# Version_04.net
KiCad netlist of a schematic drawn in EAGLE
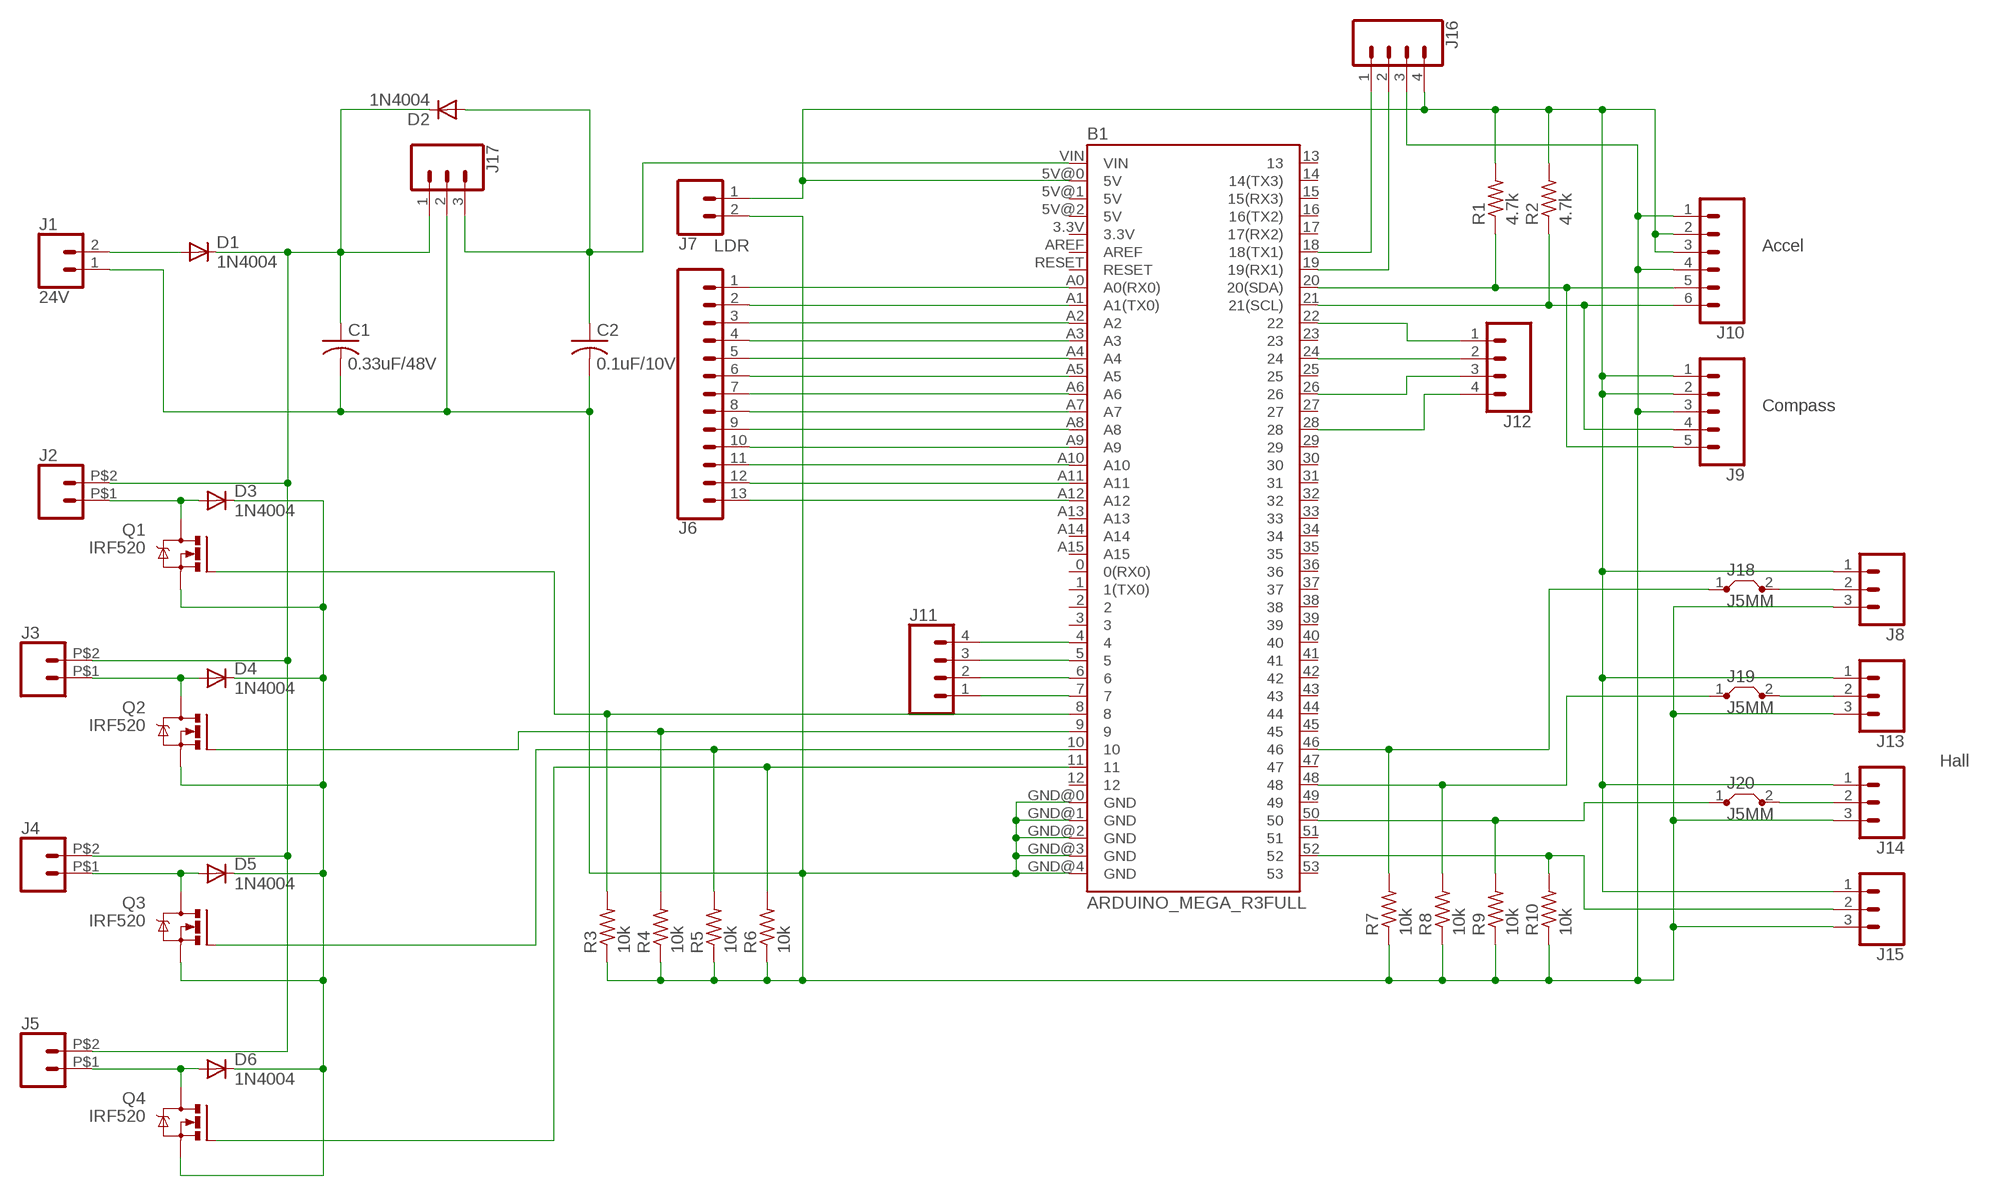
[diagram p0: schematic, sheet 1]

(export (version "E")
  (design (tool "Eeschema 10.0.6"))
  (components
    (comp (ref "B1")
      (value "ARDUINO_MEGA_R3FULL")
      (footprint "eagle-import:ARDUINO_MEGA")
      (libsource (lib "eagle-import") (part "ARDUINO_MEGA_R3FULL"))
    )
    (comp (ref "C1")
      (value "0.33uF/48V")
      (footprint "eagle-import:C050-075X075")
      (libsource (lib "eagle-import") (part "C-US050-075X075"))
    )
    (comp (ref "C2")
      (value "0.1uF/10V")
      (footprint "eagle-import:C025-060X050")
      (libsource (lib "eagle-import") (part "C-US025-060X050"))
    )
    (comp (ref "D1")
      (value "1N4004")
      (footprint "eagle-import:DO41-10")
      (libsource (lib "eagle-import") (part "1N4004"))
    )
    (comp (ref "D2")
      (value "1N4004")
      (footprint "eagle-import:DO41-10")
      (libsource (lib "eagle-import") (part "1N4004"))
    )
    (comp (ref "D3")
      (value "1N4004")
      (footprint "eagle-import:DO41-10")
      (libsource (lib "eagle-import") (part "1N4004"))
    )
    (comp (ref "D4")
      (value "1N4004")
      (footprint "eagle-import:DO41-10")
      (libsource (lib "eagle-import") (part "1N4004"))
    )
    (comp (ref "D5")
      (value "1N4004")
      (footprint "eagle-import:DO41-10")
      (libsource (lib "eagle-import") (part "1N4004"))
    )
    (comp (ref "D6")
      (value "1N4004")
      (footprint "eagle-import:DO41-10")
      (libsource (lib "eagle-import") (part "1N4004"))
    )
    (comp (ref "J1")
      (value "24V")
      (footprint "eagle-import:SCREWTERMINAL-3.5MM-2_LOCK")
      (libsource (lib "eagle-import") (part "CONN_023.5MM_LOCK"))
    )
    (comp (ref "J2")
      (value "CONN_02PTH2")
      (footprint "eagle-import:1X02_BIG")
      (libsource (lib "eagle-import") (part "CONN_02PTH2"))
    )
    (comp (ref "J3")
      (value "CONN_02PTH2")
      (footprint "eagle-import:1X02_BIG")
      (libsource (lib "eagle-import") (part "CONN_02PTH2"))
    )
    (comp (ref "J4")
      (value "CONN_02PTH2")
      (footprint "eagle-import:1X02_BIG")
      (libsource (lib "eagle-import") (part "CONN_02PTH2"))
    )
    (comp (ref "J5")
      (value "CONN_02PTH2")
      (footprint "eagle-import:1X02_BIG")
      (libsource (lib "eagle-import") (part "CONN_02PTH2"))
    )
    (comp (ref "J6")
      (value "CONN_13LONGPADS")
      (footprint "eagle-import:1X13-LONGPADS")
      (libsource (lib "eagle-import") (part "CONN_13LONGPADS"))
    )
    (comp (ref "J7")
      (value "CONN_02LOCK_LONGPADS")
      (footprint "eagle-import:1X02_LOCK_LONGPADS")
      (libsource (lib "eagle-import") (part "CONN_02LOCK_LONGPADS"))
    )
    (comp (ref "J8")
      (value "CONN_03LONGPADS")
      (footprint "eagle-import:1X03_LONGPADS")
      (libsource (lib "eagle-import") (part "CONN_03LONGPADS"))
    )
    (comp (ref "J9")
      (value "CONN_05PTH_LONGPADS")
      (footprint "eagle-import:1X05_LONGPADS")
      (libsource (lib "eagle-import") (part "CONN_05PTH_LONGPADS"))
    )
    (comp (ref "J10")
      (value "CONN_06LONGPADS")
      (footprint "eagle-import:1X06_LONGPADS")
      (libsource (lib "eagle-import") (part "CONN_06LONGPADS"))
    )
    (comp (ref "J11")
      (value "CONN_04LONGPADS")
      (footprint "eagle-import:1X04_LONGPADS")
      (libsource (lib "eagle-import") (part "CONN_04LONGPADS"))
    )
    (comp (ref "J12")
      (value "CONN_04LONGPADS")
      (footprint "eagle-import:1X04_LONGPADS")
      (libsource (lib "eagle-import") (part "CONN_04LONGPADS"))
    )
    (comp (ref "J13")
      (value "CONN_03LONGPADS")
      (footprint "eagle-import:1X03_LONGPADS")
      (libsource (lib "eagle-import") (part "CONN_03LONGPADS"))
    )
    (comp (ref "J14")
      (value "CONN_03LONGPADS")
      (footprint "eagle-import:1X03_LONGPADS")
      (libsource (lib "eagle-import") (part "CONN_03LONGPADS"))
    )
    (comp (ref "J15")
      (value "CONN_03LONGPADS")
      (footprint "eagle-import:1X03_LONGPADS")
      (libsource (lib "eagle-import") (part "CONN_03LONGPADS"))
    )
    (comp (ref "J16")
      (value "CONN_04LONGPADS")
      (footprint "eagle-import:1X04_LONGPADS")
      (libsource (lib "eagle-import") (part "CONN_04LONGPADS"))
    )
    (comp (ref "J17")
      (value "CONN_03LONGPADS")
      (footprint "eagle-import:1X03_LONGPADS")
      (libsource (lib "eagle-import") (part "CONN_03LONGPADS"))
    )
    (comp (ref "J18")
      (value "J5MM")
      (footprint "eagle-import:05")
      (libsource (lib "eagle-import") (part "J5MM"))
    )
    (comp (ref "J19")
      (value "J5MM")
      (footprint "eagle-import:05")
      (libsource (lib "eagle-import") (part "J5MM"))
    )
    (comp (ref "J20")
      (value "J5MM")
      (footprint "eagle-import:05")
      (libsource (lib "eagle-import") (part "J5MM"))
    )
    (comp (ref "Q1")
      (value "IRF520")
      (footprint "eagle-import:TO220BV")
      (libsource (lib "eagle-import") (part "IRF520"))
    )
    (comp (ref "Q2")
      (value "IRF520")
      (footprint "eagle-import:TO220BV")
      (libsource (lib "eagle-import") (part "IRF520"))
    )
    (comp (ref "Q3")
      (value "IRF520")
      (footprint "eagle-import:TO220BV")
      (libsource (lib "eagle-import") (part "IRF520"))
    )
    (comp (ref "Q4")
      (value "IRF520")
      (footprint "eagle-import:TO220BV")
      (libsource (lib "eagle-import") (part "IRF520"))
    )
    (comp (ref "R1")
      (value "4.7k")
      (footprint "eagle-import:0207_7")
      (libsource (lib "eagle-import") (part "resistor_R-US_0207/7"))
    )
    (comp (ref "R2")
      (value "4.7k")
      (footprint "eagle-import:0207_7")
      (libsource (lib "eagle-import") (part "resistor_R-US_0207/7"))
    )
    (comp (ref "R3")
      (value "10k")
      (footprint "eagle-import:0207_10")
      (libsource (lib "eagle-import") (part "rcl_R-US_0207/10"))
    )
    (comp (ref "R4")
      (value "10k")
      (footprint "eagle-import:0207_10")
      (libsource (lib "eagle-import") (part "rcl_R-US_0207/10"))
    )
    (comp (ref "R5")
      (value "10k")
      (footprint "eagle-import:0207_10")
      (libsource (lib "eagle-import") (part "rcl_R-US_0207/10"))
    )
    (comp (ref "R6")
      (value "10k")
      (footprint "eagle-import:0207_10")
      (libsource (lib "eagle-import") (part "rcl_R-US_0207/10"))
    )
    (comp (ref "R7")
      (value "10k")
      (footprint "eagle-import:0207_10")
      (libsource (lib "eagle-import") (part "R-US_0207/10"))
    )
    (comp (ref "R8")
      (value "10k")
      (footprint "eagle-import:0207_10")
      (libsource (lib "eagle-import") (part "R-US_0207/10"))
    )
    (comp (ref "R9")
      (value "10k")
      (footprint "eagle-import:0207_10")
      (libsource (lib "eagle-import") (part "R-US_0207/10"))
    )
    (comp (ref "R10")
      (value "10k")
      (footprint "eagle-import:0207_10")
      (libsource (lib "eagle-import") (part "R-US_0207/10"))
    )
  )
  (nets
    (net (code "1") (name "Net-(B1-5V-Pad5V@0)") (class "Default")
      (node (ref "B1") (pin "5V@0") (pinfunction "5V_5V@0") (pintype "bidirectional"))
      (node (ref "J10") (pin "2") (pinfunction "2_2") (pintype "passive"))
      (node (ref "J10") (pin "3") (pinfunction "3_3") (pintype "passive"))
      (node (ref "J13") (pin "1") (pinfunction "1_1") (pintype "passive"))
      (node (ref "J14") (pin "1") (pinfunction "1_1") (pintype "passive"))
      (node (ref "J15") (pin "1") (pinfunction "1_1") (pintype "passive"))
      (node (ref "J16") (pin "4") (pinfunction "4_4") (pintype "passive"))
      (node (ref "J7") (pin "1") (pinfunction "1_1") (pintype "passive"))
      (node (ref "J8") (pin "1") (pinfunction "1_1") (pintype "passive"))
      (node (ref "J9") (pin "1") (pinfunction "1_1") (pintype "passive"))
      (node (ref "J9") (pin "2") (pinfunction "2_2") (pintype "passive"))
      (node (ref "R1") (pin "2") (pinfunction "2_2") (pintype "passive"))
      (node (ref "R2") (pin "2") (pinfunction "2_2") (pintype "passive"))
    )
    (net (code "2") (name "Net-(B1-18(TX1))") (class "Default")
      (node (ref "B1") (pin "18") (pinfunction "18(TX1)_18") (pintype "bidirectional"))
      (node (ref "J16") (pin "1") (pinfunction "1_1") (pintype "passive"))
    )
    (net (code "3") (name "Net-(B1-19(RX1))") (class "Default")
      (node (ref "B1") (pin "19") (pinfunction "19(RX1)_19") (pintype "bidirectional"))
      (node (ref "J16") (pin "2") (pinfunction "2_2") (pintype "passive"))
    )
    (net (code "4") (name "Net-(B1-20(SDA))") (class "Default")
      (node (ref "B1") (pin "20") (pinfunction "20(SDA)_20") (pintype "bidirectional"))
      (node (ref "J10") (pin "5") (pinfunction "5_5") (pintype "passive"))
      (node (ref "J9") (pin "5") (pinfunction "5_5") (pintype "passive"))
      (node (ref "R1") (pin "1") (pinfunction "1_1") (pintype "passive"))
    )
    (net (code "5") (name "Net-(B1-21(SCL))") (class "Default")
      (node (ref "B1") (pin "21") (pinfunction "21(SCL)_21") (pintype "bidirectional"))
      (node (ref "J10") (pin "6") (pinfunction "6_6") (pintype "passive"))
      (node (ref "J9") (pin "4") (pinfunction "4_4") (pintype "passive"))
      (node (ref "R2") (pin "1") (pinfunction "1_1") (pintype "passive"))
    )
    (net (code "6") (name "Net-(B1-A0(RX0))") (class "Default")
      (node (ref "B1") (pin "A0") (pinfunction "A0(RX0)_A0") (pintype "bidirectional"))
      (node (ref "J6") (pin "1") (pinfunction "1_1") (pintype "passive"))
    )
    (net (code "7") (name "Net-(B1-A1(TX0))") (class "Default")
      (node (ref "B1") (pin "A1") (pinfunction "A1(TX0)_A1") (pintype "bidirectional"))
      (node (ref "J6") (pin "2") (pinfunction "2_2") (pintype "passive"))
    )
    (net (code "8") (name "Net-(B1-GND-PadGND@0)") (class "Default")
      (node (ref "B1") (pin "GND@0") (pinfunction "GND_GND@0") (pintype "bidirectional"))
      (node (ref "B1") (pin "GND@1") (pinfunction "GND_GND@1") (pintype "bidirectional"))
      (node (ref "B1") (pin "GND@2") (pinfunction "GND_GND@2") (pintype "bidirectional"))
      (node (ref "B1") (pin "GND@3") (pinfunction "GND_GND@3") (pintype "bidirectional"))
      (node (ref "B1") (pin "GND@4") (pinfunction "GND_GND@4") (pintype "bidirectional"))
      (node (ref "C1") (pin "2") (pinfunction "2_2") (pintype "passive"))
      (node (ref "C2") (pin "2") (pinfunction "2_2") (pintype "passive"))
      (node (ref "J1") (pin "1") (pinfunction "1_1") (pintype "passive"))
      (node (ref "J10") (pin "1") (pinfunction "1_1") (pintype "passive"))
      (node (ref "J10") (pin "4") (pinfunction "4_4") (pintype "passive"))
      (node (ref "J13") (pin "3") (pinfunction "3_3") (pintype "passive"))
      (node (ref "J14") (pin "3") (pinfunction "3_3") (pintype "passive"))
      (node (ref "J15") (pin "3") (pinfunction "3_3") (pintype "passive"))
      (node (ref "J16") (pin "3") (pinfunction "3_3") (pintype "passive"))
      (node (ref "J17") (pin "2") (pinfunction "2_2") (pintype "passive"))
      (node (ref "J7") (pin "2") (pinfunction "2_2") (pintype "passive"))
      (node (ref "J8") (pin "3") (pinfunction "3_3") (pintype "passive"))
      (node (ref "J9") (pin "3") (pinfunction "3_3") (pintype "passive"))
      (node (ref "R10") (pin "1") (pinfunction "1_1") (pintype "passive"))
      (node (ref "R3") (pin "1") (pinfunction "1_1") (pintype "passive"))
      (node (ref "R4") (pin "1") (pinfunction "1_1") (pintype "passive"))
      (node (ref "R5") (pin "1") (pinfunction "1_1") (pintype "passive"))
      (node (ref "R6") (pin "1") (pinfunction "1_1") (pintype "passive"))
      (node (ref "R7") (pin "1") (pinfunction "1_1") (pintype "passive"))
      (node (ref "R8") (pin "1") (pinfunction "1_1") (pintype "passive"))
      (node (ref "R9") (pin "1") (pinfunction "1_1") (pintype "passive"))
    )
    (net (code "9") (name "Net-(B1-Pad4)") (class "Default")
      (node (ref "B1") (pin "4") (pinfunction "4_4") (pintype "bidirectional"))
      (node (ref "J11") (pin "4") (pinfunction "4_4") (pintype "passive"))
    )
    (net (code "10") (name "Net-(B1-Pad5)") (class "Default")
      (node (ref "B1") (pin "5") (pinfunction "5_5") (pintype "bidirectional"))
      (node (ref "J11") (pin "3") (pinfunction "3_3") (pintype "passive"))
    )
    (net (code "11") (name "Net-(B1-Pad6)") (class "Default")
      (node (ref "B1") (pin "6") (pinfunction "6_6") (pintype "bidirectional"))
      (node (ref "J11") (pin "2") (pinfunction "2_2") (pintype "passive"))
    )
    (net (code "12") (name "Net-(B1-Pad7)") (class "Default")
      (node (ref "B1") (pin "7") (pinfunction "7_7") (pintype "bidirectional"))
      (node (ref "J11") (pin "1") (pinfunction "1_1") (pintype "passive"))
    )
    (net (code "13") (name "Net-(B1-Pad8)") (class "Default")
      (node (ref "B1") (pin "8") (pinfunction "8_8") (pintype "bidirectional"))
      (node (ref "Q1") (pin "G") (pinfunction "G_G") (pintype "passive"))
      (node (ref "R3") (pin "2") (pinfunction "2_2") (pintype "passive"))
    )
    (net (code "14") (name "Net-(B1-Pad9)") (class "Default")
      (node (ref "B1") (pin "9") (pinfunction "9_9") (pintype "bidirectional"))
      (node (ref "Q2") (pin "G") (pinfunction "G_G") (pintype "passive"))
      (node (ref "R4") (pin "2") (pinfunction "2_2") (pintype "passive"))
    )
    (net (code "15") (name "Net-(B1-Pad10)") (class "Default")
      (node (ref "B1") (pin "10") (pinfunction "10_10") (pintype "bidirectional"))
      (node (ref "Q3") (pin "G") (pinfunction "G_G") (pintype "passive"))
      (node (ref "R5") (pin "2") (pinfunction "2_2") (pintype "passive"))
    )
    (net (code "16") (name "Net-(B1-Pad11)") (class "Default")
      (node (ref "B1") (pin "11") (pinfunction "11_11") (pintype "bidirectional"))
      (node (ref "Q4") (pin "G") (pinfunction "G_G") (pintype "passive"))
      (node (ref "R6") (pin "2") (pinfunction "2_2") (pintype "passive"))
    )
    (net (code "17") (name "Net-(B1-Pad22)") (class "Default")
      (node (ref "B1") (pin "22") (pinfunction "22_22") (pintype "bidirectional"))
      (node (ref "J12") (pin "1") (pinfunction "1_1") (pintype "passive"))
    )
    (net (code "18") (name "Net-(B1-Pad24)") (class "Default")
      (node (ref "B1") (pin "24") (pinfunction "24_24") (pintype "bidirectional"))
      (node (ref "J12") (pin "2") (pinfunction "2_2") (pintype "passive"))
    )
    (net (code "19") (name "Net-(B1-Pad26)") (class "Default")
      (node (ref "B1") (pin "26") (pinfunction "26_26") (pintype "bidirectional"))
      (node (ref "J12") (pin "3") (pinfunction "3_3") (pintype "passive"))
    )
    (net (code "20") (name "Net-(B1-Pad28)") (class "Default")
      (node (ref "B1") (pin "28") (pinfunction "28_28") (pintype "bidirectional"))
      (node (ref "J12") (pin "4") (pinfunction "4_4") (pintype "passive"))
    )
    (net (code "21") (name "Net-(B1-Pad46)") (class "Default")
      (node (ref "B1") (pin "46") (pinfunction "46_46") (pintype "bidirectional"))
      (node (ref "J18") (pin "1") (pinfunction "1_1") (pintype "passive"))
      (node (ref "R7") (pin "2") (pinfunction "2_2") (pintype "passive"))
    )
    (net (code "22") (name "Net-(B1-Pad48)") (class "Default")
      (node (ref "B1") (pin "48") (pinfunction "48_48") (pintype "bidirectional"))
      (node (ref "J19") (pin "1") (pinfunction "1_1") (pintype "passive"))
      (node (ref "R8") (pin "2") (pinfunction "2_2") (pintype "passive"))
    )
    (net (code "23") (name "Net-(B1-Pad50)") (class "Default")
      (node (ref "B1") (pin "50") (pinfunction "50_50") (pintype "bidirectional"))
      (node (ref "J20") (pin "1") (pinfunction "1_1") (pintype "passive"))
      (node (ref "R9") (pin "2") (pinfunction "2_2") (pintype "passive"))
    )
    (net (code "24") (name "Net-(B1-Pad52)") (class "Default")
      (node (ref "B1") (pin "52") (pinfunction "52_52") (pintype "bidirectional"))
      (node (ref "J15") (pin "2") (pinfunction "2_2") (pintype "passive"))
      (node (ref "R10") (pin "2") (pinfunction "2_2") (pintype "passive"))
    )
    (net (code "25") (name "Net-(B1-PadA2)") (class "Default")
      (node (ref "B1") (pin "A2") (pinfunction "A2_A2") (pintype "bidirectional"))
      (node (ref "J6") (pin "3") (pinfunction "3_3") (pintype "passive"))
    )
    (net (code "26") (name "Net-(B1-PadA3)") (class "Default")
      (node (ref "B1") (pin "A3") (pinfunction "A3_A3") (pintype "bidirectional"))
      (node (ref "J6") (pin "4") (pinfunction "4_4") (pintype "passive"))
    )
    (net (code "27") (name "Net-(B1-PadA4)") (class "Default")
      (node (ref "B1") (pin "A4") (pinfunction "A4_A4") (pintype "bidirectional"))
      (node (ref "J6") (pin "5") (pinfunction "5_5") (pintype "passive"))
    )
    (net (code "28") (name "Net-(B1-PadA5)") (class "Default")
      (node (ref "B1") (pin "A5") (pinfunction "A5_A5") (pintype "bidirectional"))
      (node (ref "J6") (pin "6") (pinfunction "6_6") (pintype "passive"))
    )
    (net (code "29") (name "Net-(B1-PadA6)") (class "Default")
      (node (ref "B1") (pin "A6") (pinfunction "A6_A6") (pintype "bidirectional"))
      (node (ref "J6") (pin "7") (pinfunction "7_7") (pintype "passive"))
    )
    (net (code "30") (name "Net-(B1-PadA7)") (class "Default")
      (node (ref "B1") (pin "A7") (pinfunction "A7_A7") (pintype "bidirectional"))
      (node (ref "J6") (pin "8") (pinfunction "8_8") (pintype "passive"))
    )
    (net (code "31") (name "Net-(B1-PadA8)") (class "Default")
      (node (ref "B1") (pin "A8") (pinfunction "A8_A8") (pintype "bidirectional"))
      (node (ref "J6") (pin "9") (pinfunction "9_9") (pintype "passive"))
    )
    (net (code "32") (name "Net-(B1-PadA9)") (class "Default")
      (node (ref "B1") (pin "A9") (pinfunction "A9_A9") (pintype "bidirectional"))
      (node (ref "J6") (pin "10") (pinfunction "10_10") (pintype "passive"))
    )
    (net (code "33") (name "Net-(B1-PadA10)") (class "Default")
      (node (ref "B1") (pin "A10") (pinfunction "A10_A10") (pintype "bidirectional"))
      (node (ref "J6") (pin "11") (pinfunction "11_11") (pintype "passive"))
    )
    (net (code "34") (name "Net-(B1-PadA11)") (class "Default")
      (node (ref "B1") (pin "A11") (pinfunction "A11_A11") (pintype "bidirectional"))
      (node (ref "J6") (pin "12") (pinfunction "12_12") (pintype "passive"))
    )
    (net (code "35") (name "Net-(B1-PadA12)") (class "Default")
      (node (ref "B1") (pin "A12") (pinfunction "A12_A12") (pintype "bidirectional"))
      (node (ref "J6") (pin "13") (pinfunction "13_13") (pintype "passive"))
    )
    (net (code "36") (name "Net-(B1-PadVIN)") (class "Default")
      (node (ref "B1") (pin "VIN") (pinfunction "VIN_VIN") (pintype "bidirectional"))
      (node (ref "C2") (pin "1") (pinfunction "1_1") (pintype "passive"))
      (node (ref "D2") (pin "A") (pinfunction "A_A") (pintype "passive"))
      (node (ref "J17") (pin "3") (pinfunction "3_3") (pintype "passive"))
    )
    (net (code "37") (name "Net-(D1-PadA)") (class "Default")
      (node (ref "D1") (pin "A") (pinfunction "A_A") (pintype "passive"))
      (node (ref "J1") (pin "2") (pinfunction "2_2") (pintype "passive"))
    )
    (net (code "38") (name "Net-(D3-PadC)") (class "Default")
      (node (ref "D3") (pin "C") (pinfunction "C_C") (pintype "passive"))
      (node (ref "D4") (pin "C") (pinfunction "C_C") (pintype "passive"))
      (node (ref "D5") (pin "C") (pinfunction "C_C") (pintype "passive"))
      (node (ref "D6") (pin "C") (pinfunction "C_C") (pintype "passive"))
      (node (ref "Q1") (pin "S") (pinfunction "S_S") (pintype "passive"))
      (node (ref "Q2") (pin "S") (pinfunction "S_S") (pintype "passive"))
      (node (ref "Q3") (pin "S") (pinfunction "S_S") (pintype "passive"))
      (node (ref "Q4") (pin "S") (pinfunction "S_S") (pintype "passive"))
    )
    (net (code "39") (name "Net-(J2-1)") (class "Default")
      (node (ref "D3") (pin "A") (pinfunction "A_A") (pintype "passive"))
      (node (ref "J2") (pin "P$1") (pinfunction "1_P$1") (pintype "passive"))
      (node (ref "Q1") (pin "D") (pinfunction "D_D") (pintype "passive"))
    )
    (net (code "40") (name "Net-(J2-2)") (class "Default")
      (node (ref "C1") (pin "1") (pinfunction "1_1") (pintype "passive"))
      (node (ref "D1") (pin "C") (pinfunction "C_C") (pintype "passive"))
      (node (ref "D2") (pin "C") (pinfunction "C_C") (pintype "passive"))
      (node (ref "J17") (pin "1") (pinfunction "1_1") (pintype "passive"))
      (node (ref "J2") (pin "P$2") (pinfunction "2_P$2") (pintype "passive"))
      (node (ref "J3") (pin "P$2") (pinfunction "2_P$2") (pintype "passive"))
      (node (ref "J4") (pin "P$2") (pinfunction "2_P$2") (pintype "passive"))
      (node (ref "J5") (pin "P$2") (pinfunction "2_P$2") (pintype "passive"))
    )
    (net (code "41") (name "Net-(J3-1)") (class "Default")
      (node (ref "D4") (pin "A") (pinfunction "A_A") (pintype "passive"))
      (node (ref "J3") (pin "P$1") (pinfunction "1_P$1") (pintype "passive"))
      (node (ref "Q2") (pin "D") (pinfunction "D_D") (pintype "passive"))
    )
    (net (code "42") (name "Net-(J4-1)") (class "Default")
      (node (ref "D5") (pin "A") (pinfunction "A_A") (pintype "passive"))
      (node (ref "J4") (pin "P$1") (pinfunction "1_P$1") (pintype "passive"))
      (node (ref "Q3") (pin "D") (pinfunction "D_D") (pintype "passive"))
    )
    (net (code "43") (name "Net-(J5-1)") (class "Default")
      (node (ref "D6") (pin "A") (pinfunction "A_A") (pintype "passive"))
      (node (ref "J5") (pin "P$1") (pinfunction "1_P$1") (pintype "passive"))
      (node (ref "Q4") (pin "D") (pinfunction "D_D") (pintype "passive"))
    )
    (net (code "44") (name "Net-(J13-Pad2)") (class "Default")
      (node (ref "J13") (pin "2") (pinfunction "2_2") (pintype "passive"))
      (node (ref "J19") (pin "2") (pinfunction "2_2") (pintype "passive"))
    )
    (net (code "45") (name "Net-(J14-Pad2)") (class "Default")
      (node (ref "J14") (pin "2") (pinfunction "2_2") (pintype "passive"))
      (node (ref "J20") (pin "2") (pinfunction "2_2") (pintype "passive"))
    )
    (net (code "46") (name "Net-(J18-Pad2)") (class "Default")
      (node (ref "J18") (pin "2") (pinfunction "2_2") (pintype "passive"))
      (node (ref "J8") (pin "2") (pinfunction "2_2") (pintype "passive"))
    )
    (net (code "47") (name "unconnected-(B1-0(RX0)-Pad0)") (class "Default")
      (node (ref "B1") (pin "0") (pinfunction "0(RX0)_0") (pintype "bidirectional"))
    )
    (net (code "48") (name "unconnected-(B1-1(TX0)-Pad1)") (class "Default")
      (node (ref "B1") (pin "1") (pinfunction "1(TX0)_1") (pintype "bidirectional"))
    )
    (net (code "49") (name "unconnected-(B1-5V-Pad5V@1)") (class "Default")
      (node (ref "B1") (pin "5V@1") (pinfunction "5V_5V@1") (pintype "bidirectional"))
    )
    (net (code "50") (name "unconnected-(B1-5V-Pad5V@2)") (class "Default")
      (node (ref "B1") (pin "5V@2") (pinfunction "5V_5V@2") (pintype "bidirectional"))
    )
    (net (code "51") (name "unconnected-(B1-14(TX3)-Pad14)") (class "Default")
      (node (ref "B1") (pin "14") (pinfunction "14(TX3)_14") (pintype "bidirectional"))
    )
    (net (code "52") (name "unconnected-(B1-15(RX3)-Pad15)") (class "Default")
      (node (ref "B1") (pin "15") (pinfunction "15(RX3)_15") (pintype "bidirectional"))
    )
    (net (code "53") (name "unconnected-(B1-16(TX2)-Pad16)") (class "Default")
      (node (ref "B1") (pin "16") (pinfunction "16(TX2)_16") (pintype "bidirectional"))
    )
    (net (code "54") (name "unconnected-(B1-17(RX2)-Pad17)") (class "Default")
      (node (ref "B1") (pin "17") (pinfunction "17(RX2)_17") (pintype "bidirectional"))
    )
    (net (code "55") (name "unconnected-(B1-Pad2)") (class "Default")
      (node (ref "B1") (pin "2") (pinfunction "2_2") (pintype "bidirectional"))
    )
    (net (code "56") (name "unconnected-(B1-Pad3)") (class "Default")
      (node (ref "B1") (pin "3") (pinfunction "3_3") (pintype "bidirectional"))
    )
    (net (code "57") (name "unconnected-(B1-Pad3.3V)") (class "Default")
      (node (ref "B1") (pin "3.3V") (pinfunction "3.3V_3.3V") (pintype "bidirectional"))
    )
    (net (code "58") (name "unconnected-(B1-Pad12)") (class "Default")
      (node (ref "B1") (pin "12") (pinfunction "12_12") (pintype "bidirectional"))
    )
    (net (code "59") (name "unconnected-(B1-Pad13)") (class "Default")
      (node (ref "B1") (pin "13") (pinfunction "13_13") (pintype "bidirectional"))
    )
    (net (code "60") (name "unconnected-(B1-Pad23)") (class "Default")
      (node (ref "B1") (pin "23") (pinfunction "23_23") (pintype "bidirectional"))
    )
    (net (code "61") (name "unconnected-(B1-Pad25)") (class "Default")
      (node (ref "B1") (pin "25") (pinfunction "25_25") (pintype "bidirectional"))
    )
    (net (code "62") (name "unconnected-(B1-Pad27)") (class "Default")
      (node (ref "B1") (pin "27") (pinfunction "27_27") (pintype "bidirectional"))
    )
    (net (code "63") (name "unconnected-(B1-Pad29)") (class "Default")
      (node (ref "B1") (pin "29") (pinfunction "29_29") (pintype "bidirectional"))
    )
    (net (code "64") (name "unconnected-(B1-Pad30)") (class "Default")
      (node (ref "B1") (pin "30") (pinfunction "30_30") (pintype "bidirectional"))
    )
    (net (code "65") (name "unconnected-(B1-Pad31)") (class "Default")
      (node (ref "B1") (pin "31") (pinfunction "31_31") (pintype "bidirectional"))
    )
    (net (code "66") (name "unconnected-(B1-Pad32)") (class "Default")
      (node (ref "B1") (pin "32") (pinfunction "32_32") (pintype "bidirectional"))
    )
    (net (code "67") (name "unconnected-(B1-Pad33)") (class "Default")
      (node (ref "B1") (pin "33") (pinfunction "33_33") (pintype "bidirectional"))
    )
    (net (code "68") (name "unconnected-(B1-Pad34)") (class "Default")
      (node (ref "B1") (pin "34") (pinfunction "34_34") (pintype "bidirectional"))
    )
    (net (code "69") (name "unconnected-(B1-Pad35)") (class "Default")
      (node (ref "B1") (pin "35") (pinfunction "35_35") (pintype "bidirectional"))
    )
    (net (code "70") (name "unconnected-(B1-Pad36)") (class "Default")
      (node (ref "B1") (pin "36") (pinfunction "36_36") (pintype "bidirectional"))
    )
    (net (code "71") (name "unconnected-(B1-Pad37)") (class "Default")
      (node (ref "B1") (pin "37") (pinfunction "37_37") (pintype "bidirectional"))
    )
    (net (code "72") (name "unconnected-(B1-Pad38)") (class "Default")
      (node (ref "B1") (pin "38") (pinfunction "38_38") (pintype "bidirectional"))
    )
    (net (code "73") (name "unconnected-(B1-Pad39)") (class "Default")
      (node (ref "B1") (pin "39") (pinfunction "39_39") (pintype "bidirectional"))
    )
    (net (code "74") (name "unconnected-(B1-Pad40)") (class "Default")
      (node (ref "B1") (pin "40") (pinfunction "40_40") (pintype "bidirectional"))
    )
    (net (code "75") (name "unconnected-(B1-Pad41)") (class "Default")
      (node (ref "B1") (pin "41") (pinfunction "41_41") (pintype "bidirectional"))
    )
    (net (code "76") (name "unconnected-(B1-Pad42)") (class "Default")
      (node (ref "B1") (pin "42") (pinfunction "42_42") (pintype "bidirectional"))
    )
    (net (code "77") (name "unconnected-(B1-Pad43)") (class "Default")
      (node (ref "B1") (pin "43") (pinfunction "43_43") (pintype "bidirectional"))
    )
    (net (code "78") (name "unconnected-(B1-Pad44)") (class "Default")
      (node (ref "B1") (pin "44") (pinfunction "44_44") (pintype "bidirectional"))
    )
    (net (code "79") (name "unconnected-(B1-Pad45)") (class "Default")
      (node (ref "B1") (pin "45") (pinfunction "45_45") (pintype "bidirectional"))
    )
    (net (code "80") (name "unconnected-(B1-Pad47)") (class "Default")
      (node (ref "B1") (pin "47") (pinfunction "47_47") (pintype "bidirectional"))
    )
    (net (code "81") (name "unconnected-(B1-Pad49)") (class "Default")
      (node (ref "B1") (pin "49") (pinfunction "49_49") (pintype "bidirectional"))
    )
    (net (code "82") (name "unconnected-(B1-Pad51)") (class "Default")
      (node (ref "B1") (pin "51") (pinfunction "51_51") (pintype "bidirectional"))
    )
    (net (code "83") (name "unconnected-(B1-Pad53)") (class "Default")
      (node (ref "B1") (pin "53") (pinfunction "53_53") (pintype "bidirectional"))
    )
    (net (code "84") (name "unconnected-(B1-PadA13)") (class "Default")
      (node (ref "B1") (pin "A13") (pinfunction "A13_A13") (pintype "bidirectional"))
    )
    (net (code "85") (name "unconnected-(B1-PadA14)") (class "Default")
      (node (ref "B1") (pin "A14") (pinfunction "A14_A14") (pintype "bidirectional"))
    )
    (net (code "86") (name "unconnected-(B1-PadA15)") (class "Default")
      (node (ref "B1") (pin "A15") (pinfunction "A15_A15") (pintype "bidirectional"))
    )
    (net (code "87") (name "unconnected-(B1-PadAREF)") (class "Default")
      (node (ref "B1") (pin "AREF") (pinfunction "AREF_AREF") (pintype "bidirectional"))
    )
    (net (code "88") (name "unconnected-(B1-PadRESET)") (class "Default")
      (node (ref "B1") (pin "RESET") (pinfunction "RESET_RESET") (pintype "bidirectional"))
    )
  )
)
